# BUS.net
KiCad netlist of a schematic drawn in EAGLE
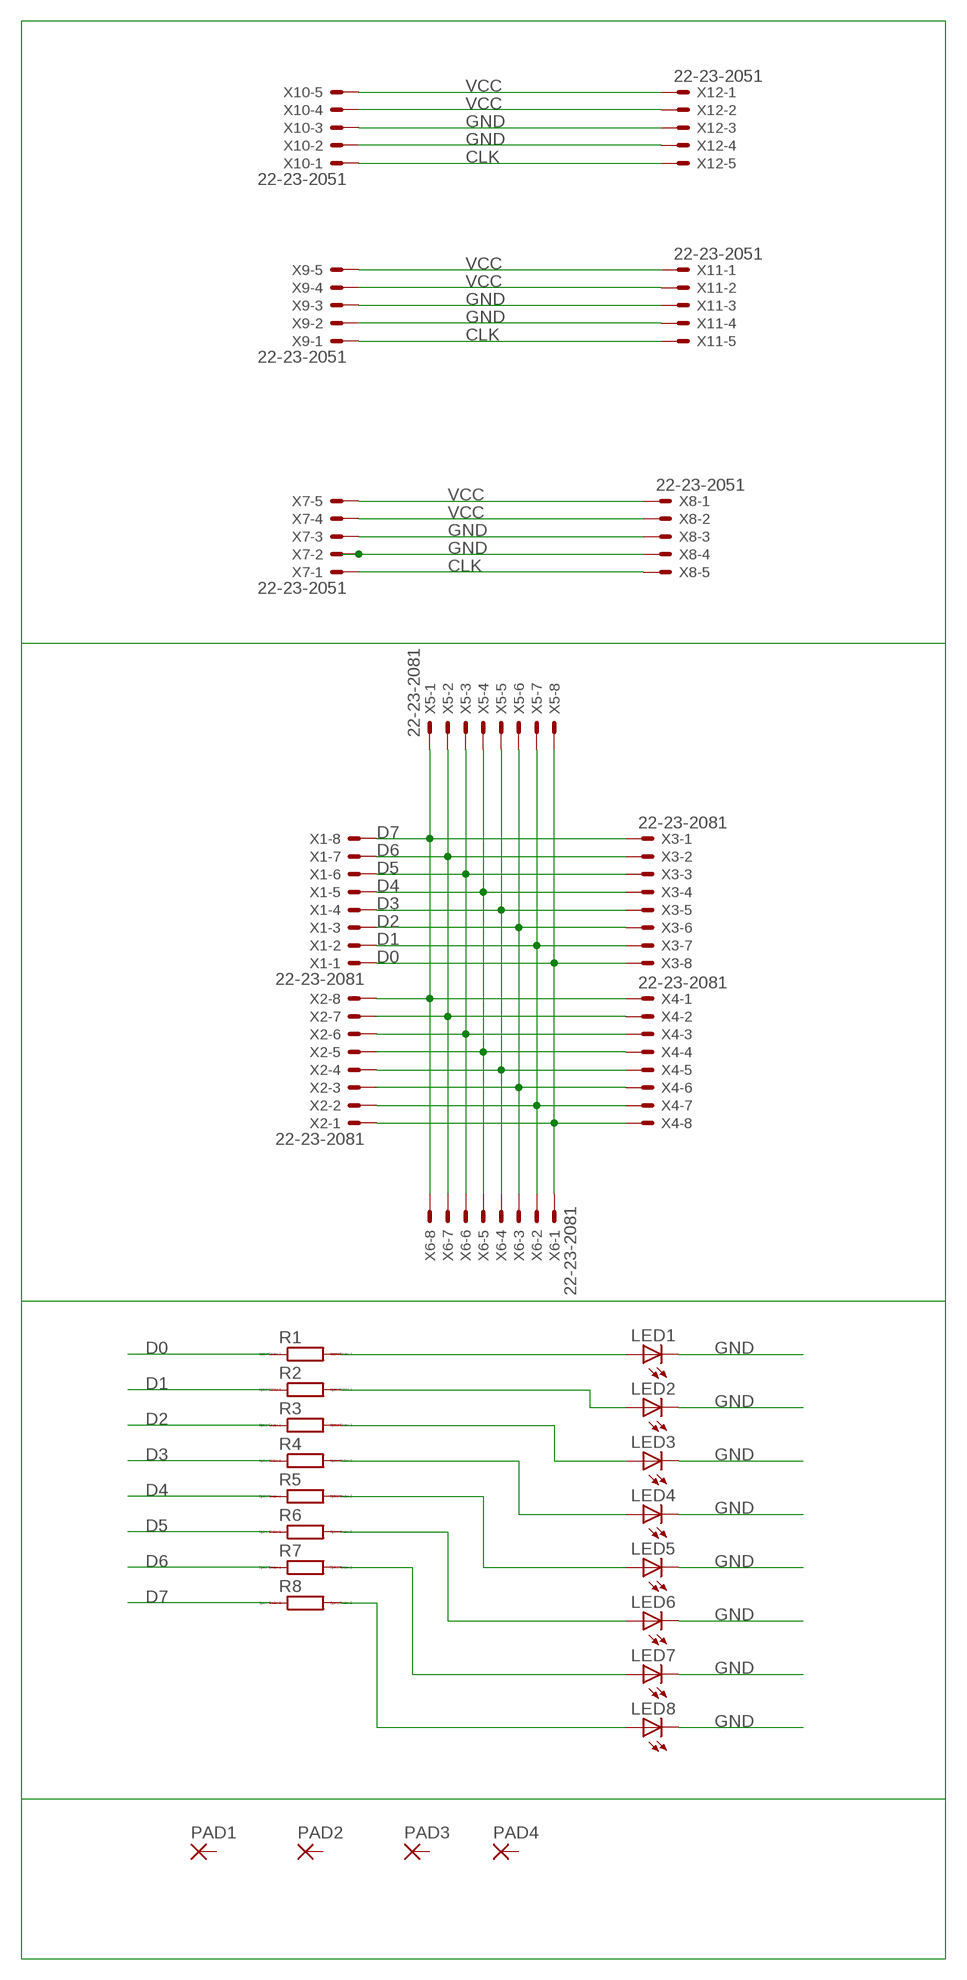
[diagram p0: schematic, sheet 1]

(export (version "E")
  (design (tool "Eeschema 10.0.6"))
  (components
    (comp (ref "LED1")
      (value "LED5MM")
      (footprint "eagle-import:LED5MM")
      (libsource (lib "eagle-import") (part "LED5MM"))
    )
    (comp (ref "LED2")
      (value "LED5MM")
      (footprint "eagle-import:LED5MM")
      (libsource (lib "eagle-import") (part "LED5MM"))
    )
    (comp (ref "LED3")
      (value "LED5MM")
      (footprint "eagle-import:LED5MM")
      (libsource (lib "eagle-import") (part "LED5MM"))
    )
    (comp (ref "LED4")
      (value "LED5MM")
      (footprint "eagle-import:LED5MM")
      (libsource (lib "eagle-import") (part "LED5MM"))
    )
    (comp (ref "LED5")
      (value "LED5MM")
      (footprint "eagle-import:LED5MM")
      (libsource (lib "eagle-import") (part "LED5MM"))
    )
    (comp (ref "LED6")
      (value "LED5MM")
      (footprint "eagle-import:LED5MM")
      (libsource (lib "eagle-import") (part "LED5MM"))
    )
    (comp (ref "LED7")
      (value "LED5MM")
      (footprint "eagle-import:LED5MM")
      (libsource (lib "eagle-import") (part "LED5MM"))
    )
    (comp (ref "LED8")
      (value "LED5MM")
      (footprint "eagle-import:LED5MM")
      (libsource (lib "eagle-import") (part "LED5MM"))
    )
    (comp (ref "PAD1")
      (value "3,17/1,1")
      (footprint "eagle-import:3,17_1,1")
      (libsource (lib "eagle-import") (part "3,17/1,1"))
    )
    (comp (ref "PAD2")
      (value "3,17/1,1")
      (footprint "eagle-import:3,17_1,1")
      (libsource (lib "eagle-import") (part "3,17/1,1"))
    )
    (comp (ref "PAD3")
      (value "3,17/1,1")
      (footprint "eagle-import:3,17_1,1")
      (libsource (lib "eagle-import") (part "3,17/1,1"))
    )
    (comp (ref "PAD4")
      (value "3,17/1,1")
      (footprint "eagle-import:3,17_1,1")
      (libsource (lib "eagle-import") (part "3,17/1,1"))
    )
    (comp (ref "R1")
      (value "R0207/10")
      (footprint "eagle-import:0207_10")
      (libsource (lib "eagle-import") (part "R0207/10"))
    )
    (comp (ref "R2")
      (value "R0207/10")
      (footprint "eagle-import:0207_10")
      (libsource (lib "eagle-import") (part "R0207/10"))
    )
    (comp (ref "R3")
      (value "R0207/10")
      (footprint "eagle-import:0207_10")
      (libsource (lib "eagle-import") (part "R0207/10"))
    )
    (comp (ref "R4")
      (value "R0207/10")
      (footprint "eagle-import:0207_10")
      (libsource (lib "eagle-import") (part "R0207/10"))
    )
    (comp (ref "R5")
      (value "R0207/10")
      (footprint "eagle-import:0207_10")
      (libsource (lib "eagle-import") (part "R0207/10"))
    )
    (comp (ref "R6")
      (value "R0207/10")
      (footprint "eagle-import:0207_10")
      (libsource (lib "eagle-import") (part "R0207/10"))
    )
    (comp (ref "R7")
      (value "R0207/10")
      (footprint "eagle-import:0207_10")
      (libsource (lib "eagle-import") (part "R0207/10"))
    )
    (comp (ref "R8")
      (value "R0207/10")
      (footprint "eagle-import:0207_10")
      (libsource (lib "eagle-import") (part "R0207/10"))
    )
    (comp (ref "X1")
      (value "22-23-2081")
      (footprint "eagle-import:22-23-2081")
      (fields (field (name "MF") "MOLEX"))
      (libsource (lib "eagle-import") (part "22-23-2081"))
    )
    (comp (ref "X2")
      (value "22-23-2081")
      (footprint "eagle-import:22-23-2081")
      (fields (field (name "MF") "MOLEX"))
      (libsource (lib "eagle-import") (part "22-23-2081"))
    )
    (comp (ref "X3")
      (value "22-23-2081")
      (footprint "eagle-import:22-23-2081")
      (fields (field (name "MF") "MOLEX"))
      (libsource (lib "eagle-import") (part "22-23-2081"))
    )
    (comp (ref "X4")
      (value "22-23-2081")
      (footprint "eagle-import:22-23-2081")
      (fields (field (name "MF") "MOLEX"))
      (libsource (lib "eagle-import") (part "22-23-2081"))
    )
    (comp (ref "X5")
      (value "22-23-2081")
      (footprint "eagle-import:22-23-2081")
      (fields (field (name "MF") "MOLEX"))
      (libsource (lib "eagle-import") (part "22-23-2081"))
    )
    (comp (ref "X6")
      (value "22-23-2081")
      (footprint "eagle-import:22-23-2081")
      (fields (field (name "MF") "MOLEX"))
      (libsource (lib "eagle-import") (part "22-23-2081"))
    )
    (comp (ref "X7")
      (value "22-23-2051")
      (footprint "eagle-import:22-23-2051")
      (fields (field (name "MF") "MOLEX"))
      (libsource (lib "eagle-import") (part "22-23-2051"))
    )
    (comp (ref "X8")
      (value "22-23-2051")
      (footprint "eagle-import:22-23-2051")
      (fields (field (name "MF") "MOLEX"))
      (libsource (lib "eagle-import") (part "22-23-2051"))
    )
    (comp (ref "X9")
      (value "22-23-2051")
      (footprint "eagle-import:22-23-2051")
      (fields (field (name "MF") "MOLEX"))
      (libsource (lib "eagle-import") (part "22-23-2051"))
    )
    (comp (ref "X10")
      (value "22-23-2051")
      (footprint "eagle-import:22-23-2051")
      (fields (field (name "MF") "MOLEX"))
      (libsource (lib "eagle-import") (part "22-23-2051"))
    )
    (comp (ref "X11")
      (value "22-23-2051")
      (footprint "eagle-import:22-23-2051")
      (fields (field (name "MF") "MOLEX"))
      (libsource (lib "eagle-import") (part "22-23-2051"))
    )
    (comp (ref "X12")
      (value "22-23-2051")
      (footprint "eagle-import:22-23-2051")
      (fields (field (name "MF") "MOLEX"))
      (libsource (lib "eagle-import") (part "22-23-2051"))
    )
  )
  (nets
    (net (code "1") (name "/CLK") (class "Default")
      (node (ref "X10") (pin "1") (pinfunction "S_1") (pintype "passive"))
      (node (ref "X11") (pin "5") (pinfunction "S_5") (pintype "passive"))
      (node (ref "X12") (pin "5") (pinfunction "S_5") (pintype "passive"))
      (node (ref "X7") (pin "1") (pinfunction "S_1") (pintype "passive"))
      (node (ref "X8") (pin "5") (pinfunction "S_5") (pintype "passive"))
      (node (ref "X9") (pin "1") (pinfunction "S_1") (pintype "passive"))
    )
    (net (code "2") (name "/D0") (class "Default")
      (node (ref "R1") (pin "1") (pinfunction "1_1") (pintype "passive"))
      (node (ref "X1") (pin "1") (pinfunction "S_1") (pintype "passive"))
      (node (ref "X2") (pin "1") (pinfunction "S_1") (pintype "passive"))
      (node (ref "X3") (pin "8") (pinfunction "S_8") (pintype "passive"))
      (node (ref "X4") (pin "8") (pinfunction "S_8") (pintype "passive"))
      (node (ref "X5") (pin "8") (pinfunction "S_8") (pintype "passive"))
      (node (ref "X6") (pin "1") (pinfunction "S_1") (pintype "passive"))
    )
    (net (code "3") (name "/D1") (class "Default")
      (node (ref "R2") (pin "1") (pinfunction "1_1") (pintype "passive"))
      (node (ref "X1") (pin "2") (pinfunction "S_2") (pintype "passive"))
      (node (ref "X2") (pin "2") (pinfunction "S_2") (pintype "passive"))
      (node (ref "X3") (pin "7") (pinfunction "S_7") (pintype "passive"))
      (node (ref "X4") (pin "7") (pinfunction "S_7") (pintype "passive"))
      (node (ref "X5") (pin "7") (pinfunction "S_7") (pintype "passive"))
      (node (ref "X6") (pin "2") (pinfunction "S_2") (pintype "passive"))
    )
    (net (code "4") (name "/D2") (class "Default")
      (node (ref "R3") (pin "1") (pinfunction "1_1") (pintype "passive"))
      (node (ref "X1") (pin "3") (pinfunction "S_3") (pintype "passive"))
      (node (ref "X2") (pin "3") (pinfunction "S_3") (pintype "passive"))
      (node (ref "X3") (pin "6") (pinfunction "S_6") (pintype "passive"))
      (node (ref "X4") (pin "6") (pinfunction "S_6") (pintype "passive"))
      (node (ref "X5") (pin "6") (pinfunction "S_6") (pintype "passive"))
      (node (ref "X6") (pin "3") (pinfunction "S_3") (pintype "passive"))
    )
    (net (code "5") (name "/D3") (class "Default")
      (node (ref "R4") (pin "1") (pinfunction "1_1") (pintype "passive"))
      (node (ref "X1") (pin "4") (pinfunction "S_4") (pintype "passive"))
      (node (ref "X2") (pin "4") (pinfunction "S_4") (pintype "passive"))
      (node (ref "X3") (pin "5") (pinfunction "S_5") (pintype "passive"))
      (node (ref "X4") (pin "5") (pinfunction "S_5") (pintype "passive"))
      (node (ref "X5") (pin "5") (pinfunction "S_5") (pintype "passive"))
      (node (ref "X6") (pin "4") (pinfunction "S_4") (pintype "passive"))
    )
    (net (code "6") (name "/D4") (class "Default")
      (node (ref "R5") (pin "1") (pinfunction "1_1") (pintype "passive"))
      (node (ref "X1") (pin "5") (pinfunction "S_5") (pintype "passive"))
      (node (ref "X2") (pin "5") (pinfunction "S_5") (pintype "passive"))
      (node (ref "X3") (pin "4") (pinfunction "S_4") (pintype "passive"))
      (node (ref "X4") (pin "4") (pinfunction "S_4") (pintype "passive"))
      (node (ref "X5") (pin "4") (pinfunction "S_4") (pintype "passive"))
      (node (ref "X6") (pin "5") (pinfunction "S_5") (pintype "passive"))
    )
    (net (code "7") (name "/D5") (class "Default")
      (node (ref "R6") (pin "1") (pinfunction "1_1") (pintype "passive"))
      (node (ref "X1") (pin "6") (pinfunction "S_6") (pintype "passive"))
      (node (ref "X2") (pin "6") (pinfunction "S_6") (pintype "passive"))
      (node (ref "X3") (pin "3") (pinfunction "S_3") (pintype "passive"))
      (node (ref "X4") (pin "3") (pinfunction "S_3") (pintype "passive"))
      (node (ref "X5") (pin "3") (pinfunction "S_3") (pintype "passive"))
      (node (ref "X6") (pin "6") (pinfunction "S_6") (pintype "passive"))
    )
    (net (code "8") (name "/D6") (class "Default")
      (node (ref "R7") (pin "1") (pinfunction "1_1") (pintype "passive"))
      (node (ref "X1") (pin "7") (pinfunction "S_7") (pintype "passive"))
      (node (ref "X2") (pin "7") (pinfunction "S_7") (pintype "passive"))
      (node (ref "X3") (pin "2") (pinfunction "S_2") (pintype "passive"))
      (node (ref "X4") (pin "2") (pinfunction "S_2") (pintype "passive"))
      (node (ref "X5") (pin "2") (pinfunction "S_2") (pintype "passive"))
      (node (ref "X6") (pin "7") (pinfunction "S_7") (pintype "passive"))
    )
    (net (code "9") (name "/D7") (class "Default")
      (node (ref "R8") (pin "1") (pinfunction "1_1") (pintype "passive"))
      (node (ref "X1") (pin "8") (pinfunction "S_8") (pintype "passive"))
      (node (ref "X2") (pin "8") (pinfunction "S_8") (pintype "passive"))
      (node (ref "X3") (pin "1") (pinfunction "S_1") (pintype "passive"))
      (node (ref "X4") (pin "1") (pinfunction "S_1") (pintype "passive"))
      (node (ref "X5") (pin "1") (pinfunction "S_1") (pintype "passive"))
      (node (ref "X6") (pin "8") (pinfunction "S_8") (pintype "passive"))
    )
    (net (code "10") (name "/GND") (class "Default")
      (node (ref "LED1") (pin "K") (pinfunction "C_K") (pintype "passive"))
      (node (ref "LED2") (pin "K") (pinfunction "C_K") (pintype "passive"))
      (node (ref "LED3") (pin "K") (pinfunction "C_K") (pintype "passive"))
      (node (ref "LED4") (pin "K") (pinfunction "C_K") (pintype "passive"))
      (node (ref "LED5") (pin "K") (pinfunction "C_K") (pintype "passive"))
      (node (ref "LED6") (pin "K") (pinfunction "C_K") (pintype "passive"))
      (node (ref "LED7") (pin "K") (pinfunction "C_K") (pintype "passive"))
      (node (ref "LED8") (pin "K") (pinfunction "C_K") (pintype "passive"))
      (node (ref "X10") (pin "2") (pinfunction "S_2") (pintype "passive"))
      (node (ref "X10") (pin "3") (pinfunction "S_3") (pintype "passive"))
      (node (ref "X11") (pin "3") (pinfunction "S_3") (pintype "passive"))
      (node (ref "X11") (pin "4") (pinfunction "S_4") (pintype "passive"))
      (node (ref "X12") (pin "3") (pinfunction "S_3") (pintype "passive"))
      (node (ref "X12") (pin "4") (pinfunction "S_4") (pintype "passive"))
      (node (ref "X7") (pin "2") (pinfunction "S_2") (pintype "passive"))
      (node (ref "X7") (pin "3") (pinfunction "S_3") (pintype "passive"))
      (node (ref "X8") (pin "3") (pinfunction "S_3") (pintype "passive"))
      (node (ref "X8") (pin "4") (pinfunction "S_4") (pintype "passive"))
      (node (ref "X9") (pin "2") (pinfunction "S_2") (pintype "passive"))
      (node (ref "X9") (pin "3") (pinfunction "S_3") (pintype "passive"))
    )
    (net (code "11") (name "/VCC") (class "Default")
      (node (ref "X10") (pin "4") (pinfunction "S_4") (pintype "passive"))
      (node (ref "X10") (pin "5") (pinfunction "S_5") (pintype "passive"))
      (node (ref "X11") (pin "1") (pinfunction "S_1") (pintype "passive"))
      (node (ref "X11") (pin "2") (pinfunction "S_2") (pintype "passive"))
      (node (ref "X12") (pin "1") (pinfunction "S_1") (pintype "passive"))
      (node (ref "X12") (pin "2") (pinfunction "S_2") (pintype "passive"))
      (node (ref "X7") (pin "4") (pinfunction "S_4") (pintype "passive"))
      (node (ref "X7") (pin "5") (pinfunction "S_5") (pintype "passive"))
      (node (ref "X8") (pin "1") (pinfunction "S_1") (pintype "passive"))
      (node (ref "X8") (pin "2") (pinfunction "S_2") (pintype "passive"))
      (node (ref "X9") (pin "4") (pinfunction "S_4") (pintype "passive"))
      (node (ref "X9") (pin "5") (pinfunction "S_5") (pintype "passive"))
    )
    (net (code "12") (name "Net-(LED1-PadA)") (class "Default")
      (node (ref "LED1") (pin "A") (pinfunction "A_A") (pintype "passive"))
      (node (ref "R1") (pin "2") (pinfunction "2_2") (pintype "passive"))
    )
    (net (code "13") (name "Net-(LED2-PadA)") (class "Default")
      (node (ref "LED2") (pin "A") (pinfunction "A_A") (pintype "passive"))
      (node (ref "R2") (pin "2") (pinfunction "2_2") (pintype "passive"))
    )
    (net (code "14") (name "Net-(LED3-PadA)") (class "Default")
      (node (ref "LED3") (pin "A") (pinfunction "A_A") (pintype "passive"))
      (node (ref "R3") (pin "2") (pinfunction "2_2") (pintype "passive"))
    )
    (net (code "15") (name "Net-(LED4-PadA)") (class "Default")
      (node (ref "LED4") (pin "A") (pinfunction "A_A") (pintype "passive"))
      (node (ref "R4") (pin "2") (pinfunction "2_2") (pintype "passive"))
    )
    (net (code "16") (name "Net-(LED5-PadA)") (class "Default")
      (node (ref "LED5") (pin "A") (pinfunction "A_A") (pintype "passive"))
      (node (ref "R5") (pin "2") (pinfunction "2_2") (pintype "passive"))
    )
    (net (code "17") (name "Net-(LED6-PadA)") (class "Default")
      (node (ref "LED6") (pin "A") (pinfunction "A_A") (pintype "passive"))
      (node (ref "R6") (pin "2") (pinfunction "2_2") (pintype "passive"))
    )
    (net (code "18") (name "Net-(LED7-PadA)") (class "Default")
      (node (ref "LED7") (pin "A") (pinfunction "A_A") (pintype "passive"))
      (node (ref "R7") (pin "2") (pinfunction "2_2") (pintype "passive"))
    )
    (net (code "19") (name "Net-(LED8-PadA)") (class "Default")
      (node (ref "LED8") (pin "A") (pinfunction "A_A") (pintype "passive"))
      (node (ref "R8") (pin "2") (pinfunction "2_2") (pintype "passive"))
    )
    (net (code "20") (name "unconnected-(PAD1-P-Pad1)") (class "Default")
      (node (ref "PAD1") (pin "1") (pinfunction "P_1") (pintype "passive"))
    )
    (net (code "21") (name "unconnected-(PAD2-P-Pad1)") (class "Default")
      (node (ref "PAD2") (pin "1") (pinfunction "P_1") (pintype "passive"))
    )
    (net (code "22") (name "unconnected-(PAD3-P-Pad1)") (class "Default")
      (node (ref "PAD3") (pin "1") (pinfunction "P_1") (pintype "passive"))
    )
    (net (code "23") (name "unconnected-(PAD4-P-Pad1)") (class "Default")
      (node (ref "PAD4") (pin "1") (pinfunction "P_1") (pintype "passive"))
    )
  )
)
